# INC-MBPCM1-01.net
KiCad netlist of a schematic drawn in Altium Designer
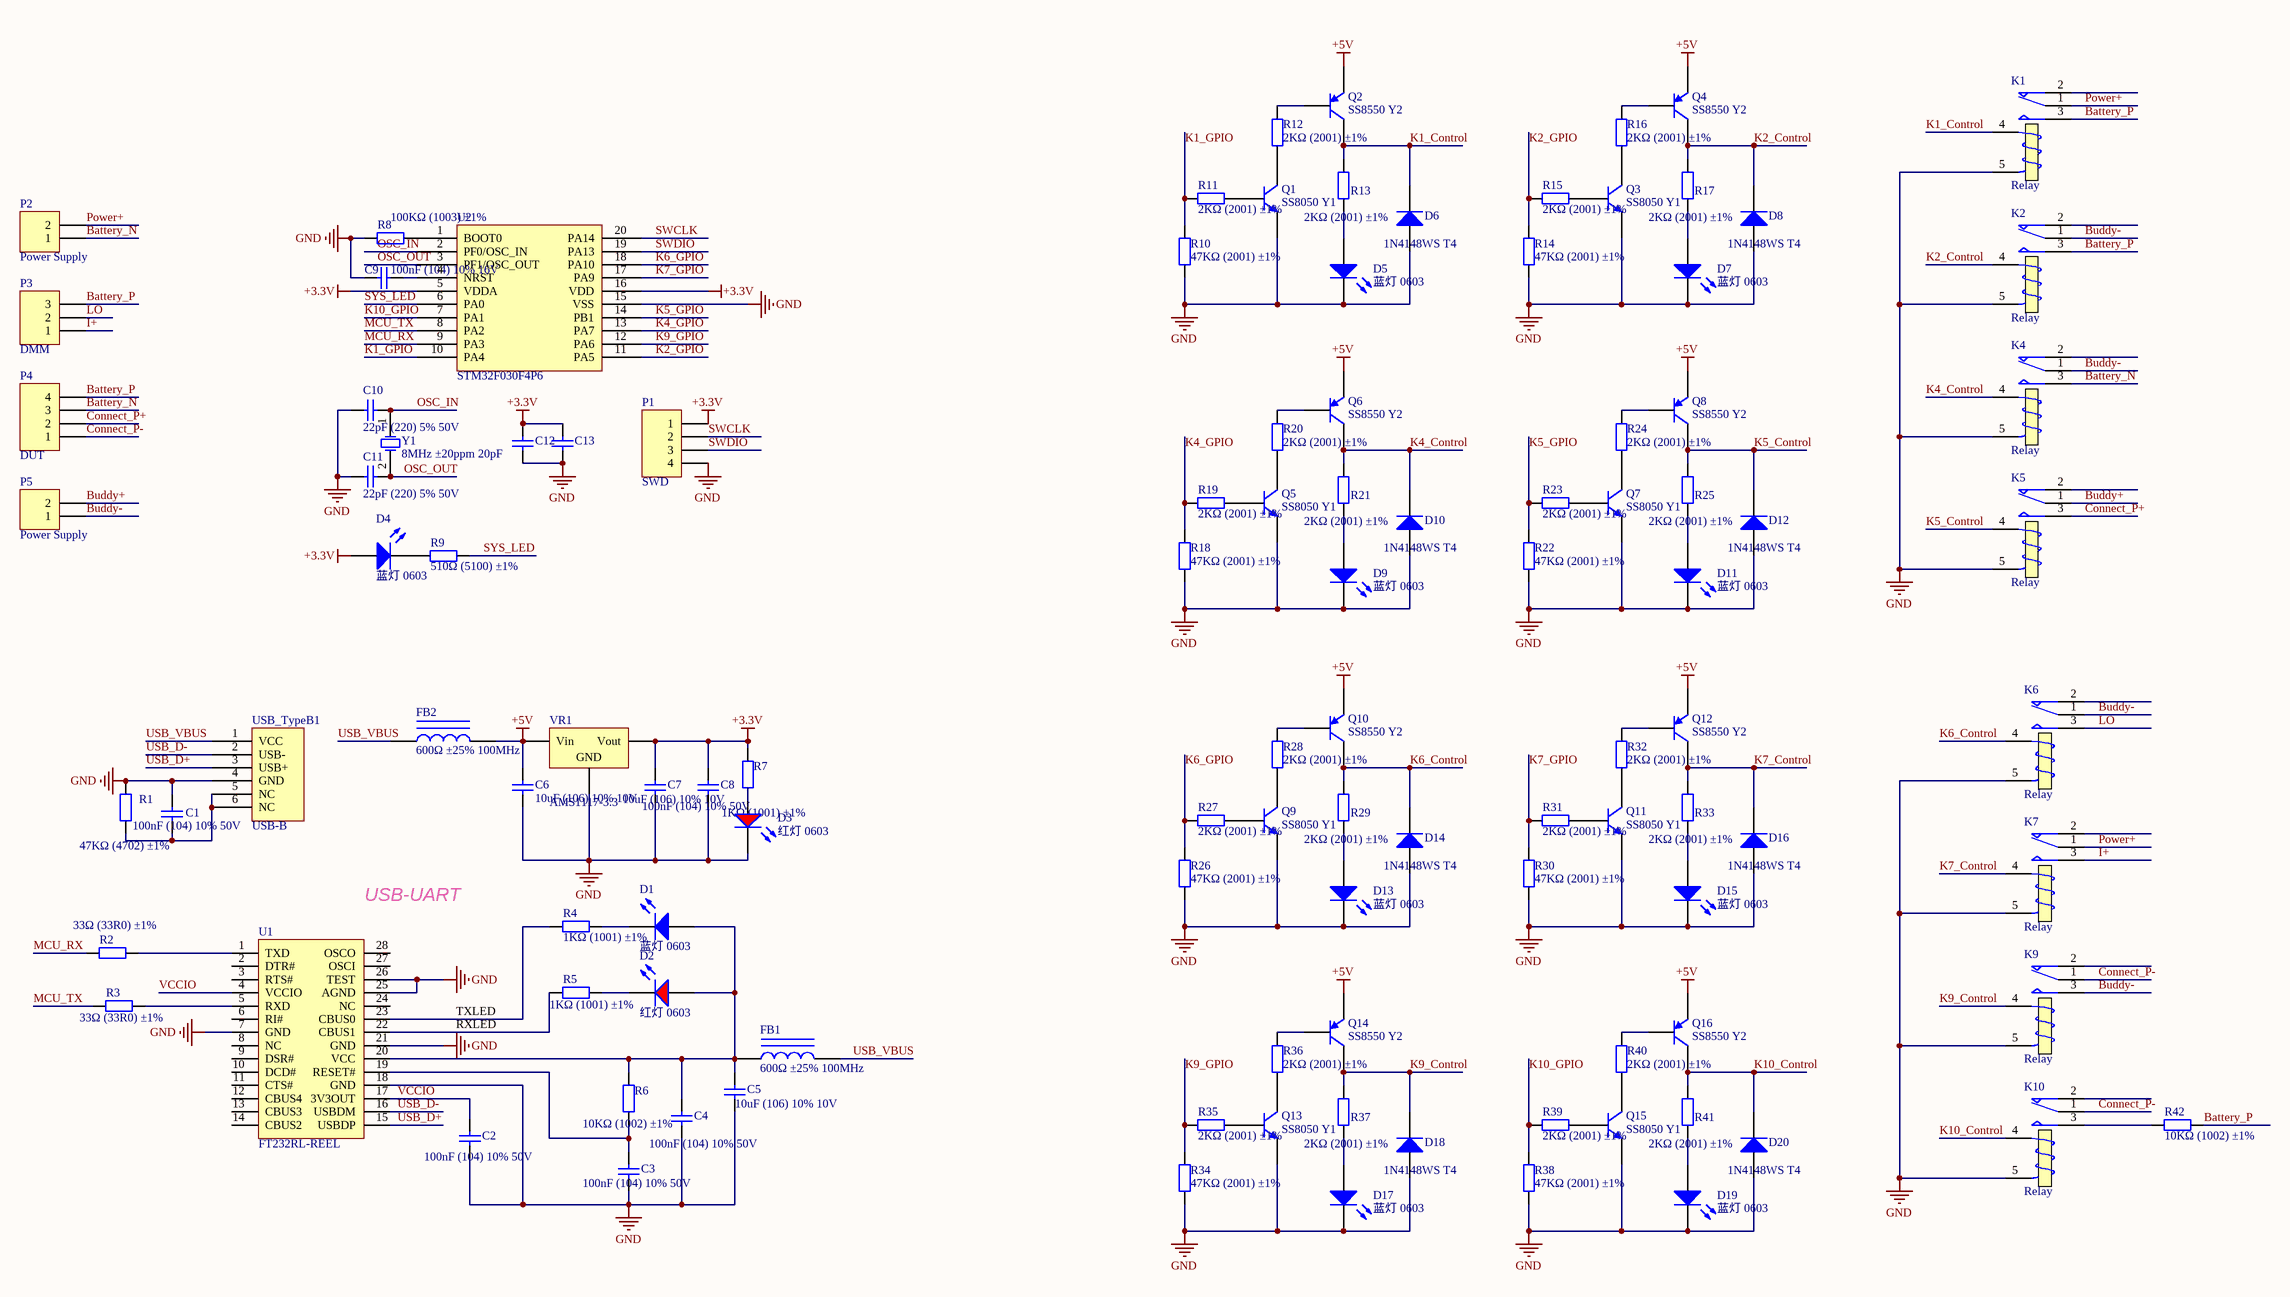
[diagram p0: INC-MBPCM1-01.SchDoc]

(export (version "E")
  (design (tool "Eeschema 10.0.6"))
  (components
    (comp (ref "C1")
      (value "100nF (104) 10% 50V")
      (footprint "0603_C")
      (description "贴片电容")
      (libsource (lib "Miscellaneous Devices LC") (part "0603 100nF (104) 10% 50V"))
    )
    (comp (ref "C2")
      (value "100nF (104) 10% 50V")
      (footprint "0603_C")
      (description "贴片电容")
      (libsource (lib "Miscellaneous Devices LC") (part "0603 100nF (104) 10% 50V"))
    )
    (comp (ref "C3")
      (value "100nF (104) 10% 50V")
      (footprint "0603_C")
      (description "贴片电容")
      (libsource (lib "Miscellaneous Devices LC") (part "0603 100nF (104) 10% 50V"))
    )
    (comp (ref "C4")
      (value "100nF (104) 10% 50V")
      (footprint "0603_C")
      (description "贴片电容")
      (libsource (lib "Miscellaneous Devices LC") (part "0603 100nF (104) 10% 50V"))
    )
    (comp (ref "C5")
      (value "10uF (106) 10% 10V")
      (footprint "0603_C")
      (description "贴片电容")
      (libsource (lib "Miscellaneous Devices LC") (part "0603 10uF (106) 10% 10V"))
    )
    (comp (ref "C6")
      (value "10uF (106) 10% 10V")
      (footprint "0603_C")
      (description "贴片电容")
      (libsource (lib "Miscellaneous Devices LC") (part "0603 10uF (106) 10% 10V"))
    )
    (comp (ref "C7")
      (value "10uF (106) 10% 10V")
      (footprint "0603_C")
      (description "贴片电容")
      (libsource (lib "Miscellaneous Devices LC") (part "0603 10uF (106) 10% 10V"))
    )
    (comp (ref "C8")
      (value "100nF (104) 10% 50V")
      (footprint "0603_C")
      (description "贴片电容")
      (libsource (lib "Miscellaneous Devices LC") (part "0603 100nF (104) 10% 50V"))
    )
    (comp (ref "C9")
      (value "100nF (104) 10% 16V")
      (footprint "0402_C")
      (description "贴片电容")
      (libsource (lib "Miscellaneous Devices LC") (part "0402 100nF (104) 10% 16V"))
    )
    (comp (ref "C10")
      (value "22pF (220) 5% 50V")
      (footprint "0603_C")
      (description "贴片电容")
      (libsource (lib "Miscellaneous Devices LC") (part "0603 22pF (220) 5% 50V"))
    )
    (comp (ref "C11")
      (value "22pF (220) 5% 50V")
      (footprint "0603_C")
      (description "贴片电容")
      (libsource (lib "Miscellaneous Devices LC") (part "0603 22pF (220) 5% 50V"))
    )
    (comp (ref "C12")
      (value "100nF (104) 10% 16V")
      (footprint "0402_C")
      (description "贴片电容")
      (libsource (lib "Miscellaneous Devices LC") (part "0402 100nF (104) 10% 16V"))
    )
    (comp (ref "C13")
      (value "100nF (104) 10% 16V")
      (footprint "0402_C")
      (description "贴片电容")
      (libsource (lib "Miscellaneous Devices LC") (part "0402 100nF (104) 10% 16V"))
    )
    (comp (ref "D1")
      (value "蓝灯 0603")
      (footprint "0603_LED_S1")
      (description "发光二极管")
      (libsource (lib "Miscellaneous Devices LC") (part "0603 蓝灯"))
    )
    (comp (ref "D2")
      (value "红灯 0603")
      (footprint "0603_LED_S1")
      (description "发光二极管")
      (libsource (lib "Miscellaneous Devices LC") (part "0603 红灯"))
    )
    (comp (ref "D3")
      (value "红灯 0603")
      (footprint "0603_LED_S1")
      (description "发光二极管")
      (libsource (lib "Miscellaneous Devices LC") (part "0603 红灯"))
    )
    (comp (ref "D4")
      (value "蓝灯 0603")
      (footprint "0603_LED_S1")
      (description "发光二极管")
      (libsource (lib "Miscellaneous Devices LC") (part "0603 蓝灯"))
    )
    (comp (ref "D5")
      (value "蓝灯 0603")
      (footprint "0603_LED_S1")
      (description "发光二极管")
      (libsource (lib "Miscellaneous Devices LC") (part "0603 蓝灯"))
    )
    (comp (ref "D6")
      (value "1N4148WS T4")
      (footprint "SOD-323")
      (description "二极管")
      (libsource (lib "Miscellaneous Devices LC") (part "SOD-323 1N4148WS T4"))
    )
    (comp (ref "D7")
      (value "蓝灯 0603")
      (footprint "0603_LED_S1")
      (description "发光二极管")
      (libsource (lib "Miscellaneous Devices LC") (part "0603 蓝灯"))
    )
    (comp (ref "D8")
      (value "1N4148WS T4")
      (footprint "SOD-323")
      (description "二极管")
      (libsource (lib "Miscellaneous Devices LC") (part "SOD-323 1N4148WS T4"))
    )
    (comp (ref "D9")
      (value "蓝灯 0603")
      (footprint "0603_LED_S1")
      (description "发光二极管")
      (libsource (lib "Miscellaneous Devices LC") (part "0603 蓝灯"))
    )
    (comp (ref "D10")
      (value "1N4148WS T4")
      (footprint "SOD-323")
      (description "二极管")
      (libsource (lib "Miscellaneous Devices LC") (part "SOD-323 1N4148WS T4"))
    )
    (comp (ref "D11")
      (value "蓝灯 0603")
      (footprint "0603_LED_S1")
      (description "发光二极管")
      (libsource (lib "Miscellaneous Devices LC") (part "0603 蓝灯"))
    )
    (comp (ref "D12")
      (value "1N4148WS T4")
      (footprint "SOD-323")
      (description "二极管")
      (libsource (lib "Miscellaneous Devices LC") (part "SOD-323 1N4148WS T4"))
    )
    (comp (ref "D13")
      (value "蓝灯 0603")
      (footprint "0603_LED_S1")
      (description "发光二极管")
      (libsource (lib "Miscellaneous Devices LC") (part "0603 蓝灯"))
    )
    (comp (ref "D14")
      (value "1N4148WS T4")
      (footprint "SOD-323")
      (description "二极管")
      (libsource (lib "Miscellaneous Devices LC") (part "SOD-323 1N4148WS T4"))
    )
    (comp (ref "D15")
      (value "蓝灯 0603")
      (footprint "0603_LED_S1")
      (description "发光二极管")
      (libsource (lib "Miscellaneous Devices LC") (part "0603 蓝灯"))
    )
    (comp (ref "D16")
      (value "1N4148WS T4")
      (footprint "SOD-323")
      (description "二极管")
      (libsource (lib "Miscellaneous Devices LC") (part "SOD-323 1N4148WS T4"))
    )
    (comp (ref "D17")
      (value "蓝灯 0603")
      (footprint "0603_LED_S1")
      (description "发光二极管")
      (libsource (lib "Miscellaneous Devices LC") (part "0603 蓝灯"))
    )
    (comp (ref "D18")
      (value "1N4148WS T4")
      (footprint "SOD-323")
      (description "二极管")
      (libsource (lib "Miscellaneous Devices LC") (part "SOD-323 1N4148WS T4"))
    )
    (comp (ref "D19")
      (value "蓝灯 0603")
      (footprint "0603_LED_S1")
      (description "发光二极管")
      (libsource (lib "Miscellaneous Devices LC") (part "0603 蓝灯"))
    )
    (comp (ref "D20")
      (value "1N4148WS T4")
      (footprint "SOD-323")
      (description "二极管")
      (libsource (lib "Miscellaneous Devices LC") (part "SOD-323 1N4148WS T4"))
    )
    (comp (ref "FB1")
      (value "600Ω ±25% 100MHz")
      (footprint "0805_L")
      (description "贴片磁珠")
      (libsource (lib "Miscellaneous Devices LC") (part "0805 600Ω 25% 100MHz"))
    )
    (comp (ref "FB2")
      (value "600Ω ±25% 100MHz")
      (footprint "0805_L")
      (description "贴片磁珠")
      (libsource (lib "Miscellaneous Devices LC") (part "0805 600Ω 25% 100MHz"))
    )
    (comp (ref "K1")
      (value "Relay")
      (footprint "插件继电器 G5V-1")
      (description "SPDT Relay")
      (fields (field (name "PUBLISHER") "Altium Limited"))
      (libsource (lib "Miscellaneous Devices") (part "Relay"))
    )
    (comp (ref "K2")
      (value "Relay")
      (footprint "插件继电器 G5V-1")
      (description "SPDT Relay")
      (fields (field (name "PUBLISHER") "Altium Limited"))
      (libsource (lib "Miscellaneous Devices") (part "Relay"))
    )
    (comp (ref "K4")
      (value "Relay")
      (footprint "插件继电器 G5V-1")
      (description "SPDT Relay")
      (fields (field (name "PUBLISHER") "Altium Limited"))
      (libsource (lib "Miscellaneous Devices") (part "Relay"))
    )
    (comp (ref "K5")
      (value "Relay")
      (footprint "插件继电器 G5V-1")
      (description "SPDT Relay")
      (fields (field (name "PUBLISHER") "Altium Limited"))
      (libsource (lib "Miscellaneous Devices") (part "Relay"))
    )
    (comp (ref "K6")
      (value "Relay")
      (footprint "插件继电器 G5V-1")
      (description "SPDT Relay")
      (fields (field (name "PUBLISHER") "Altium Limited"))
      (libsource (lib "Miscellaneous Devices") (part "Relay"))
    )
    (comp (ref "K7")
      (value "Relay")
      (footprint "插件继电器 G5V-1")
      (description "SPDT Relay")
      (fields (field (name "PUBLISHER") "Altium Limited"))
      (libsource (lib "Miscellaneous Devices") (part "Relay"))
    )
    (comp (ref "K9")
      (value "Relay")
      (footprint "插件继电器 G5V-1")
      (description "SPDT Relay")
      (fields (field (name "PUBLISHER") "Altium Limited"))
      (libsource (lib "Miscellaneous Devices") (part "Relay"))
    )
    (comp (ref "K10")
      (value "Relay")
      (footprint "插件继电器 G5V-1")
      (description "SPDT Relay")
      (fields (field (name "PUBLISHER") "Altium Limited"))
      (libsource (lib "Miscellaneous Devices") (part "Relay"))
    )
    (comp (ref "P1")
      (value "SWD")
      (footprint "XH连接器 4P-2.5")
      (description "Header, 4-Pin")
      (fields (field (name "PUBLISHER") "Altium Limited"))
      (libsource (lib "Miscellaneous Connectors") (part "MHDR1X4"))
    )
    (comp (ref "P2")
      (value "Header 2")
      (footprint "WJ15EDGVC-3.81-2P")
      (description "Header, 2-Pin")
      (fields (field (name "PUBLISHER") "Altium Limited"))
      (libsource (lib "Miscellaneous Connectors") (part "Header 2"))
    )
    (comp (ref "P3")
      (value "Header 3")
      (footprint "WJ15EDGVC-3.81-3P")
      (description "Header, 3-Pin")
      (fields (field (name "PUBLISHER") "Altium Limited"))
      (libsource (lib "Miscellaneous Connectors") (part "Header 3"))
    )
    (comp (ref "P4")
      (value "Header 4")
      (footprint "WJ15EDGVC-3.81-4P")
      (description "Header, 4-Pin")
      (fields (field (name "PUBLISHER") "Altium Limited"))
      (libsource (lib "Miscellaneous Connectors") (part "Header 4"))
    )
    (comp (ref "P5")
      (value "Header 2")
      (footprint "WJ15EDGVC-3.81-2P")
      (description "Header, 2-Pin")
      (fields (field (name "PUBLISHER") "Altium Limited"))
      (libsource (lib "Miscellaneous Connectors") (part "Header 2"))
    )
    (comp (ref "Q1")
      (value "SS8050 Y1")
      (footprint "SOT-23(SOT-23-3)")
      (description "三极管")
      (libsource (lib "Miscellaneous Devices LC") (part "SOT-23 SS8050 Y1"))
    )
    (comp (ref "Q2")
      (value "SS8550 Y2")
      (footprint "SOT-23(SOT-23-3)")
      (description "三极管")
      (libsource (lib "Miscellaneous Devices LC") (part "SOT-23 SS8550 Y2"))
    )
    (comp (ref "Q3")
      (value "SS8050 Y1")
      (footprint "SOT-23(SOT-23-3)")
      (description "三极管")
      (libsource (lib "Miscellaneous Devices LC") (part "SOT-23 SS8050 Y1"))
    )
    (comp (ref "Q4")
      (value "SS8550 Y2")
      (footprint "SOT-23(SOT-23-3)")
      (description "三极管")
      (libsource (lib "Miscellaneous Devices LC") (part "SOT-23 SS8550 Y2"))
    )
    (comp (ref "Q5")
      (value "SS8050 Y1")
      (footprint "SOT-23(SOT-23-3)")
      (description "三极管")
      (libsource (lib "Miscellaneous Devices LC") (part "SOT-23 SS8050 Y1"))
    )
    (comp (ref "Q6")
      (value "SS8550 Y2")
      (footprint "SOT-23(SOT-23-3)")
      (description "三极管")
      (libsource (lib "Miscellaneous Devices LC") (part "SOT-23 SS8550 Y2"))
    )
    (comp (ref "Q7")
      (value "SS8050 Y1")
      (footprint "SOT-23(SOT-23-3)")
      (description "三极管")
      (libsource (lib "Miscellaneous Devices LC") (part "SOT-23 SS8050 Y1"))
    )
    (comp (ref "Q8")
      (value "SS8550 Y2")
      (footprint "SOT-23(SOT-23-3)")
      (description "三极管")
      (libsource (lib "Miscellaneous Devices LC") (part "SOT-23 SS8550 Y2"))
    )
    (comp (ref "Q9")
      (value "SS8050 Y1")
      (footprint "SOT-23(SOT-23-3)")
      (description "三极管")
      (libsource (lib "Miscellaneous Devices LC") (part "SOT-23 SS8050 Y1"))
    )
    (comp (ref "Q10")
      (value "SS8550 Y2")
      (footprint "SOT-23(SOT-23-3)")
      (description "三极管")
      (libsource (lib "Miscellaneous Devices LC") (part "SOT-23 SS8550 Y2"))
    )
    (comp (ref "Q11")
      (value "SS8050 Y1")
      (footprint "SOT-23(SOT-23-3)")
      (description "三极管")
      (libsource (lib "Miscellaneous Devices LC") (part "SOT-23 SS8050 Y1"))
    )
    (comp (ref "Q12")
      (value "SS8550 Y2")
      (footprint "SOT-23(SOT-23-3)")
      (description "三极管")
      (libsource (lib "Miscellaneous Devices LC") (part "SOT-23 SS8550 Y2"))
    )
    (comp (ref "Q13")
      (value "SS8050 Y1")
      (footprint "SOT-23(SOT-23-3)")
      (description "三极管")
      (libsource (lib "Miscellaneous Devices LC") (part "SOT-23 SS8050 Y1"))
    )
    (comp (ref "Q14")
      (value "SS8550 Y2")
      (footprint "SOT-23(SOT-23-3)")
      (description "三极管")
      (libsource (lib "Miscellaneous Devices LC") (part "SOT-23 SS8550 Y2"))
    )
    (comp (ref "Q15")
      (value "SS8050 Y1")
      (footprint "SOT-23(SOT-23-3)")
      (description "三极管")
      (libsource (lib "Miscellaneous Devices LC") (part "SOT-23 SS8050 Y1"))
    )
    (comp (ref "Q16")
      (value "SS8550 Y2")
      (footprint "SOT-23(SOT-23-3)")
      (description "三极管")
      (libsource (lib "Miscellaneous Devices LC") (part "SOT-23 SS8550 Y2"))
    )
    (comp (ref "R1")
      (value "47KΩ (4702) ±1%")
      (footprint "0603_R")
      (description "贴片电阻")
      (libsource (lib "Miscellaneous Devices LC") (part "0603 47KΩ (4702) 1%"))
    )
    (comp (ref "R2")
      (value "33Ω (33R0) ±1%")
      (footprint "0603_R")
      (description "贴片电阻")
      (libsource (lib "Miscellaneous Devices LC") (part "0603 330Ω (3300) 1%"))
    )
    (comp (ref "R3")
      (value "33Ω (33R0) ±1%")
      (footprint "0603_R")
      (description "贴片电阻")
      (libsource (lib "Miscellaneous Devices LC") (part "0603 330Ω (3300) 1%"))
    )
    (comp (ref "R4")
      (value "1KΩ (1001) ±1%")
      (footprint "0603_R")
      (description "贴片电阻")
      (libsource (lib "") (part "0603 1KΩ (1001) 1%_2"))
    )
    (comp (ref "R5")
      (value "1KΩ (1001) ±1%")
      (footprint "0603_R")
      (description "贴片电阻")
      (libsource (lib "Miscellaneous Devices LC") (part "0603 1KΩ (1001) 1%"))
    )
    (comp (ref "R6")
      (value "10KΩ (1002) ±1%")
      (footprint "0603_R")
      (description "贴片电阻")
      (libsource (lib "Miscellaneous Devices LC") (part "0603 10KΩ (1002) 1%"))
    )
    (comp (ref "R7")
      (value "1KΩ (1001) ±1%")
      (footprint "0603_R")
      (description "贴片电阻")
      (libsource (lib "") (part "0603 1KΩ (1001) 1%_1"))
    )
    (comp (ref "R8")
      (value "100KΩ (1003) ±1%")
      (footprint "0402_R")
      (description "贴片电阻")
      (libsource (lib "Miscellaneous Devices LC") (part "0402 100KΩ (1003) 1%"))
    )
    (comp (ref "R9")
      (value "510Ω (5100) ±1%")
      (footprint "0603_R")
      (description "贴片电阻")
      (libsource (lib "Miscellaneous Devices LC") (part "0603 510Ω (5100) 1%"))
    )
    (comp (ref "R10")
      (value "47KΩ (2001) ±1%")
      (footprint "0603_R")
      (description "贴片电阻")
      (libsource (lib "") (part "0603 2KΩ (2001) 1%_1"))
    )
    (comp (ref "R11")
      (value "2KΩ (2001) ±1%")
      (footprint "0603_R")
      (description "贴片电阻")
      (libsource (lib "Miscellaneous Devices LC") (part "0603 2KΩ (2001) 1%"))
    )
    (comp (ref "R12")
      (value "2KΩ (2001) ±1%")
      (footprint "0603_R")
      (description "贴片电阻")
      (libsource (lib "") (part "0603 2KΩ (2001) 1%_1"))
    )
    (comp (ref "R13")
      (value "2KΩ (2001) ±1%")
      (footprint "0603_R")
      (description "贴片电阻")
      (libsource (lib "") (part "0603 2KΩ (2001) 1%_2"))
    )
    (comp (ref "R14")
      (value "47KΩ (2001) ±1%")
      (footprint "0603_R")
      (description "贴片电阻")
      (libsource (lib "") (part "0603 2KΩ (2001) 1%_1"))
    )
    (comp (ref "R15")
      (value "2KΩ (2001) ±1%")
      (footprint "0603_R")
      (description "贴片电阻")
      (libsource (lib "Miscellaneous Devices LC") (part "0603 2KΩ (2001) 1%"))
    )
    (comp (ref "R16")
      (value "2KΩ (2001) ±1%")
      (footprint "0603_R")
      (description "贴片电阻")
      (libsource (lib "") (part "0603 2KΩ (2001) 1%_1"))
    )
    (comp (ref "R17")
      (value "2KΩ (2001) ±1%")
      (footprint "0603_R")
      (description "贴片电阻")
      (libsource (lib "") (part "0603 2KΩ (2001) 1%_2"))
    )
    (comp (ref "R18")
      (value "47KΩ (2001) ±1%")
      (footprint "0603_R")
      (description "贴片电阻")
      (libsource (lib "") (part "0603 2KΩ (2001) 1%_1"))
    )
    (comp (ref "R19")
      (value "2KΩ (2001) ±1%")
      (footprint "0603_R")
      (description "贴片电阻")
      (libsource (lib "Miscellaneous Devices LC") (part "0603 2KΩ (2001) 1%"))
    )
    (comp (ref "R20")
      (value "2KΩ (2001) ±1%")
      (footprint "0603_R")
      (description "贴片电阻")
      (libsource (lib "") (part "0603 2KΩ (2001) 1%_1"))
    )
    (comp (ref "R21")
      (value "2KΩ (2001) ±1%")
      (footprint "0603_R")
      (description "贴片电阻")
      (libsource (lib "") (part "0603 2KΩ (2001) 1%_2"))
    )
    (comp (ref "R22")
      (value "47KΩ (2001) ±1%")
      (footprint "0603_R")
      (description "贴片电阻")
      (libsource (lib "") (part "0603 2KΩ (2001) 1%_1"))
    )
    (comp (ref "R23")
      (value "2KΩ (2001) ±1%")
      (footprint "0603_R")
      (description "贴片电阻")
      (libsource (lib "Miscellaneous Devices LC") (part "0603 2KΩ (2001) 1%"))
    )
    (comp (ref "R24")
      (value "2KΩ (2001) ±1%")
      (footprint "0603_R")
      (description "贴片电阻")
      (libsource (lib "") (part "0603 2KΩ (2001) 1%_1"))
    )
    (comp (ref "R25")
      (value "2KΩ (2001) ±1%")
      (footprint "0603_R")
      (description "贴片电阻")
      (libsource (lib "") (part "0603 2KΩ (2001) 1%_2"))
    )
    (comp (ref "R26")
      (value "47KΩ (2001) ±1%")
      (footprint "0603_R")
      (description "贴片电阻")
      (libsource (lib "") (part "0603 2KΩ (2001) 1%_1"))
    )
    (comp (ref "R27")
      (value "2KΩ (2001) ±1%")
      (footprint "0603_R")
      (description "贴片电阻")
      (libsource (lib "Miscellaneous Devices LC") (part "0603 2KΩ (2001) 1%"))
    )
    (comp (ref "R28")
      (value "2KΩ (2001) ±1%")
      (footprint "0603_R")
      (description "贴片电阻")
      (libsource (lib "") (part "0603 2KΩ (2001) 1%_1"))
    )
    (comp (ref "R29")
      (value "2KΩ (2001) ±1%")
      (footprint "0603_R")
      (description "贴片电阻")
      (libsource (lib "") (part "0603 2KΩ (2001) 1%_2"))
    )
    (comp (ref "R30")
      (value "47KΩ (2001) ±1%")
      (footprint "0603_R")
      (description "贴片电阻")
      (libsource (lib "") (part "0603 2KΩ (2001) 1%_1"))
    )
    (comp (ref "R31")
      (value "2KΩ (2001) ±1%")
      (footprint "0603_R")
      (description "贴片电阻")
      (libsource (lib "Miscellaneous Devices LC") (part "0603 2KΩ (2001) 1%"))
    )
    (comp (ref "R32")
      (value "2KΩ (2001) ±1%")
      (footprint "0603_R")
      (description "贴片电阻")
      (libsource (lib "") (part "0603 2KΩ (2001) 1%_1"))
    )
    (comp (ref "R33")
      (value "2KΩ (2001) ±1%")
      (footprint "0603_R")
      (description "贴片电阻")
      (libsource (lib "") (part "0603 2KΩ (2001) 1%_2"))
    )
    (comp (ref "R34")
      (value "47KΩ (2001) ±1%")
      (footprint "0603_R")
      (description "贴片电阻")
      (libsource (lib "") (part "0603 2KΩ (2001) 1%_1"))
    )
    (comp (ref "R35")
      (value "2KΩ (2001) ±1%")
      (footprint "0603_R")
      (description "贴片电阻")
      (libsource (lib "Miscellaneous Devices LC") (part "0603 2KΩ (2001) 1%"))
    )
    (comp (ref "R36")
      (value "2KΩ (2001) ±1%")
      (footprint "0603_R")
      (description "贴片电阻")
      (libsource (lib "") (part "0603 2KΩ (2001) 1%_1"))
    )
    (comp (ref "R37")
      (value "2KΩ (2001) ±1%")
      (footprint "0603_R")
      (description "贴片电阻")
      (libsource (lib "") (part "0603 2KΩ (2001) 1%_2"))
    )
    (comp (ref "R38")
      (value "47KΩ (2001) ±1%")
      (footprint "0603_R")
      (description "贴片电阻")
      (libsource (lib "") (part "0603 2KΩ (2001) 1%_1"))
    )
    (comp (ref "R39")
      (value "2KΩ (2001) ±1%")
      (footprint "0603_R")
      (description "贴片电阻")
      (libsource (lib "Miscellaneous Devices LC") (part "0603 2KΩ (2001) 1%"))
    )
    (comp (ref "R40")
      (value "2KΩ (2001) ±1%")
      (footprint "0603_R")
      (description "贴片电阻")
      (libsource (lib "") (part "0603 2KΩ (2001) 1%_1"))
    )
    (comp (ref "R41")
      (value "2KΩ (2001) ±1%")
      (footprint "0603_R")
      (description "贴片电阻")
      (libsource (lib "") (part "0603 2KΩ (2001) 1%_2"))
    )
    (comp (ref "R42")
      (value "10KΩ (1002) ±1%")
      (footprint "0805_R")
      (description "贴片电阻")
      (libsource (lib "Miscellaneous Devices LC") (part "0805 10KΩ (1002) 1%"))
    )
    (comp (ref "U1")
      (value "FT232RL-REEL")
      (footprint "SSOP-28_208mil")
      (libsource (lib "GB-SCH") (part "FT232RL"))
    )
    (comp (ref "U2")
      (value "STM32F030F4P6")
      (footprint "TSSOP-20")
      (description "ARM")
      (libsource (lib "Miscellaneous Devices LC") (part "STM32F030F4P6"))
    )
    (comp (ref "USB_TypeB1")
      (value "USB-B")
      (footprint "USB_TypeB")
      (libsource (lib "GB-SCH") (part "USB-6"))
    )
    (comp (ref "VR1")
      (value "AMS1117-3.3")
      (footprint "SOT-223")
      (description "低压差线性稳压(LDO)")
      (libsource (lib "Miscellaneous Devices LC") (part "SOT-223 AMS1117-3.3"))
    )
    (comp (ref "Y1")
      (value "8MHz ±20ppm 20pF")
      (footprint "SMD-5032_2P")
      (description "贴片晶振")
      (libsource (lib "Miscellaneous Devices LC") (part "SMD-5032_2P 8MHz 20ppm 20pF"))
    )
  )
  (nets
    (net (code "1") (name "+3.3V") (class "Default")
      (node (ref "C12") (pin "2") (pinfunction "2_2") (pintype "passive"))
      (node (ref "C13") (pin "2") (pinfunction "2_2") (pintype "passive"))
      (node (ref "C7") (pin "1") (pinfunction "1_1") (pintype "passive"))
      (node (ref "C8") (pin "2") (pinfunction "2_2") (pintype "passive"))
      (node (ref "D4") (pin "A") (pinfunction "A_A") (pintype "passive"))
      (node (ref "P1") (pin "1") (pinfunction "1_1") (pintype "passive"))
      (node (ref "R7") (pin "1") (pinfunction "1_1") (pintype "passive"))
      (node (ref "U2") (pin "16") (pinfunction "VDD_16") (pintype "passive"))
      (node (ref "U2") (pin "5") (pinfunction "VDDA_5") (pintype "passive"))
      (node (ref "VR1") (pin "2") (pinfunction "Vout_2") (pintype "passive"))
    )
    (net (code "2") (name "+5V") (class "Default")
      (node (ref "C6") (pin "2") (pinfunction "2_2") (pintype "passive"))
      (node (ref "FB2") (pin "2") (pinfunction "2_2") (pintype "passive"))
      (node (ref "Q10") (pin "2") (pinfunction "E_2") (pintype "passive"))
      (node (ref "Q12") (pin "2") (pinfunction "E_2") (pintype "passive"))
      (node (ref "Q14") (pin "2") (pinfunction "E_2") (pintype "passive"))
      (node (ref "Q16") (pin "2") (pinfunction "E_2") (pintype "passive"))
      (node (ref "Q2") (pin "2") (pinfunction "E_2") (pintype "passive"))
      (node (ref "Q4") (pin "2") (pinfunction "E_2") (pintype "passive"))
      (node (ref "Q6") (pin "2") (pinfunction "E_2") (pintype "passive"))
      (node (ref "Q8") (pin "2") (pinfunction "E_2") (pintype "passive"))
      (node (ref "VR1") (pin "3") (pinfunction "Vin_3") (pintype "passive"))
    )
    (net (code "3") (name "/Battery_N") (class "Default")
      (node (ref "K4") (pin "3") (pinfunction "NO_3") (pintype "passive"))
      (node (ref "P2") (pin "1") (pinfunction "1_1") (pintype "passive"))
      (node (ref "P4") (pin "3") (pinfunction "3_3") (pintype "passive"))
    )
    (net (code "4") (name "/Battery_P") (class "Default")
      (node (ref "K1") (pin "3") (pinfunction "NO_3") (pintype "passive"))
      (node (ref "K2") (pin "3") (pinfunction "NO_3") (pintype "passive"))
      (node (ref "P3") (pin "3") (pinfunction "3_3") (pintype "passive"))
      (node (ref "P4") (pin "4") (pinfunction "4_4") (pintype "passive"))
      (node (ref "R42") (pin "2") (pinfunction "2_2") (pintype "passive"))
    )
    (net (code "5") (name "/Buddy+") (class "Default")
      (node (ref "K5") (pin "1") (pinfunction "COM_1") (pintype "passive"))
      (node (ref "P5") (pin "2") (pinfunction "2_2") (pintype "passive"))
    )
    (net (code "6") (name "/Buddy-") (class "Default")
      (node (ref "K2") (pin "1") (pinfunction "COM_1") (pintype "passive"))
      (node (ref "K4") (pin "1") (pinfunction "COM_1") (pintype "passive"))
      (node (ref "K6") (pin "1") (pinfunction "COM_1") (pintype "passive"))
      (node (ref "K9") (pin "3") (pinfunction "NO_3") (pintype "passive"))
      (node (ref "P5") (pin "1") (pinfunction "1_1") (pintype "passive"))
    )
    (net (code "7") (name "/Connect_P+") (class "Default")
      (node (ref "K5") (pin "3") (pinfunction "NO_3") (pintype "passive"))
      (node (ref "P4") (pin "2") (pinfunction "2_2") (pintype "passive"))
    )
    (net (code "8") (name "/Connect_P-") (class "Default")
      (node (ref "K10") (pin "1") (pinfunction "COM_1") (pintype "passive"))
      (node (ref "K9") (pin "1") (pinfunction "COM_1") (pintype "passive"))
      (node (ref "P4") (pin "1") (pinfunction "1_1") (pintype "passive"))
    )
    (net (code "9") (name "/I+") (class "Default")
      (node (ref "K7") (pin "3") (pinfunction "NO_3") (pintype "passive"))
      (node (ref "P3") (pin "1") (pinfunction "1_1") (pintype "passive"))
    )
    (net (code "10") (name "/K1_Control") (class "Default")
      (node (ref "D6") (pin "2") (pinfunction "K_2") (pintype "passive"))
      (node (ref "K1") (pin "4") (pinfunction "T1_4") (pintype "passive"))
      (node (ref "Q2") (pin "3") (pinfunction "C_3") (pintype "passive"))
      (node (ref "R13") (pin "1") (pinfunction "1_1") (pintype "passive"))
    )
    (net (code "11") (name "/K1_GPIO") (class "Default")
      (node (ref "R10") (pin "2") (pinfunction "2_2") (pintype "passive"))
      (node (ref "R11") (pin "2") (pinfunction "2_2") (pintype "passive"))
      (node (ref "U2") (pin "10") (pinfunction "PA4_10") (pintype "passive"))
    )
    (net (code "12") (name "/K2_Control") (class "Default")
      (node (ref "D8") (pin "2") (pinfunction "K_2") (pintype "passive"))
      (node (ref "K2") (pin "4") (pinfunction "T1_4") (pintype "passive"))
      (node (ref "Q4") (pin "3") (pinfunction "C_3") (pintype "passive"))
      (node (ref "R17") (pin "1") (pinfunction "1_1") (pintype "passive"))
    )
    (net (code "13") (name "/K2_GPIO") (class "Default")
      (node (ref "R14") (pin "2") (pinfunction "2_2") (pintype "passive"))
      (node (ref "R15") (pin "2") (pinfunction "2_2") (pintype "passive"))
      (node (ref "U2") (pin "11") (pinfunction "PA5_11") (pintype "passive"))
    )
    (net (code "14") (name "/K4_Control") (class "Default")
      (node (ref "D10") (pin "2") (pinfunction "K_2") (pintype "passive"))
      (node (ref "K4") (pin "4") (pinfunction "T1_4") (pintype "passive"))
      (node (ref "Q6") (pin "3") (pinfunction "C_3") (pintype "passive"))
      (node (ref "R21") (pin "1") (pinfunction "1_1") (pintype "passive"))
    )
    (net (code "15") (name "/K4_GPIO") (class "Default")
      (node (ref "R18") (pin "2") (pinfunction "2_2") (pintype "passive"))
      (node (ref "R19") (pin "2") (pinfunction "2_2") (pintype "passive"))
      (node (ref "U2") (pin "13") (pinfunction "PA7_13") (pintype "passive"))
    )
    (net (code "16") (name "/K5_Control") (class "Default")
      (node (ref "D12") (pin "2") (pinfunction "K_2") (pintype "passive"))
      (node (ref "K5") (pin "4") (pinfunction "T1_4") (pintype "passive"))
      (node (ref "Q8") (pin "3") (pinfunction "C_3") (pintype "passive"))
      (node (ref "R25") (pin "1") (pinfunction "1_1") (pintype "passive"))
    )
    (net (code "17") (name "/K5_GPIO") (class "Default")
      (node (ref "R22") (pin "2") (pinfunction "2_2") (pintype "passive"))
      (node (ref "R23") (pin "2") (pinfunction "2_2") (pintype "passive"))
      (node (ref "U2") (pin "14") (pinfunction "PB1_14") (pintype "passive"))
    )
    (net (code "18") (name "/K6_Control") (class "Default")
      (node (ref "D14") (pin "2") (pinfunction "K_2") (pintype "passive"))
      (node (ref "K6") (pin "4") (pinfunction "T1_4") (pintype "passive"))
      (node (ref "Q10") (pin "3") (pinfunction "C_3") (pintype "passive"))
      (node (ref "R29") (pin "1") (pinfunction "1_1") (pintype "passive"))
    )
    (net (code "19") (name "/K6_GPIO") (class "Default")
      (node (ref "R26") (pin "2") (pinfunction "2_2") (pintype "passive"))
      (node (ref "R27") (pin "2") (pinfunction "2_2") (pintype "passive"))
      (node (ref "U2") (pin "18") (pinfunction "PA10_18") (pintype "passive"))
    )
    (net (code "20") (name "/K7_Control") (class "Default")
      (node (ref "D16") (pin "2") (pinfunction "K_2") (pintype "passive"))
      (node (ref "K7") (pin "4") (pinfunction "T1_4") (pintype "passive"))
      (node (ref "Q12") (pin "3") (pinfunction "C_3") (pintype "passive"))
      (node (ref "R33") (pin "1") (pinfunction "1_1") (pintype "passive"))
    )
    (net (code "21") (name "/K7_GPIO") (class "Default")
      (node (ref "R30") (pin "2") (pinfunction "2_2") (pintype "passive"))
      (node (ref "R31") (pin "2") (pinfunction "2_2") (pintype "passive"))
      (node (ref "U2") (pin "17") (pinfunction "PA9_17") (pintype "passive"))
    )
    (net (code "22") (name "/K9_Control") (class "Default")
      (node (ref "D18") (pin "2") (pinfunction "K_2") (pintype "passive"))
      (node (ref "K9") (pin "4") (pinfunction "T1_4") (pintype "passive"))
      (node (ref "Q14") (pin "3") (pinfunction "C_3") (pintype "passive"))
      (node (ref "R37") (pin "1") (pinfunction "1_1") (pintype "passive"))
    )
    (net (code "23") (name "/K9_GPIO") (class "Default")
      (node (ref "R34") (pin "2") (pinfunction "2_2") (pintype "passive"))
      (node (ref "R35") (pin "2") (pinfunction "2_2") (pintype "passive"))
      (node (ref "U2") (pin "12") (pinfunction "PA6_12") (pintype "passive"))
    )
    (net (code "24") (name "/K10_Control") (class "Default")
      (node (ref "D20") (pin "2") (pinfunction "K_2") (pintype "passive"))
      (node (ref "K10") (pin "4") (pinfunction "T1_4") (pintype "passive"))
      (node (ref "Q16") (pin "3") (pinfunction "C_3") (pintype "passive"))
      (node (ref "R41") (pin "1") (pinfunction "1_1") (pintype "passive"))
    )
    (net (code "25") (name "/K10_GPIO") (class "Default")
      (node (ref "R38") (pin "2") (pinfunction "2_2") (pintype "passive"))
      (node (ref "R39") (pin "2") (pinfunction "2_2") (pintype "passive"))
      (node (ref "U2") (pin "7") (pinfunction "PA1_7") (pintype "passive"))
    )
    (net (code "26") (name "/LO") (class "Default")
      (node (ref "K6") (pin "3") (pinfunction "NO_3") (pintype "passive"))
      (node (ref "P3") (pin "2") (pinfunction "2_2") (pintype "passive"))
    )
    (net (code "27") (name "/MCU_RX") (class "Default")
      (node (ref "R2") (pin "1") (pinfunction "1_1") (pintype "passive"))
      (node (ref "U2") (pin "9") (pinfunction "PA3_9") (pintype "passive"))
    )
    (net (code "28") (name "/MCU_TX") (class "Default")
      (node (ref "R3") (pin "1") (pinfunction "1_1") (pintype "passive"))
      (node (ref "U2") (pin "8") (pinfunction "PA2_8") (pintype "passive"))
    )
    (net (code "29") (name "/OSC_IN") (class "Default")
      (node (ref "C10") (pin "2") (pinfunction "2_2") (pintype "passive"))
      (node (ref "U2") (pin "2") (pinfunction "PF0/OSC_IN_2") (pintype "passive"))
      (node (ref "Y1") (pin "1") (pinfunction "OSC1_1") (pintype "passive"))
    )
    (net (code "30") (name "/OSC_OUT") (class "Default")
      (node (ref "C11") (pin "2") (pinfunction "2_2") (pintype "passive"))
      (node (ref "U2") (pin "3") (pinfunction "PF1/OSC_OUT_3") (pintype "passive"))
      (node (ref "Y1") (pin "2") (pinfunction "OSC2_2") (pintype "passive"))
    )
    (net (code "31") (name "/Power+") (class "Default")
      (node (ref "K1") (pin "1") (pinfunction "COM_1") (pintype "passive"))
      (node (ref "K7") (pin "1") (pinfunction "COM_1") (pintype "passive"))
      (node (ref "P2") (pin "2") (pinfunction "2_2") (pintype "passive"))
    )
    (net (code "32") (name "/SWCLK") (class "Default")
      (node (ref "P1") (pin "2") (pinfunction "2_2") (pintype "passive"))
      (node (ref "U2") (pin "20") (pinfunction "PA14_20") (pintype "passive"))
    )
    (net (code "33") (name "/SWDIO") (class "Default")
      (node (ref "P1") (pin "3") (pinfunction "3_3") (pintype "passive"))
      (node (ref "U2") (pin "19") (pinfunction "PA13_19") (pintype "passive"))
    )
    (net (code "34") (name "/SYS_LED") (class "Default")
      (node (ref "R9") (pin "2") (pinfunction "2_2") (pintype "passive"))
      (node (ref "U2") (pin "6") (pinfunction "PA0_6") (pintype "passive"))
    )
    (net (code "35") (name "/USB_D+") (class "Default")
      (node (ref "U1") (pin "15") (pinfunction "USBDP_15") (pintype "passive"))
      (node (ref "USB_TypeB1") (pin "3") (pinfunction "USB+_3") (pintype "passive"))
    )
    (net (code "36") (name "/USB_D-") (class "Default")
      (node (ref "U1") (pin "16") (pinfunction "USBDM_16") (pintype "passive"))
      (node (ref "USB_TypeB1") (pin "2") (pinfunction "USB-_2") (pintype "passive"))
    )
    (net (code "37") (name "/USB_VBUS") (class "Default")
      (node (ref "FB1") (pin "2") (pinfunction "2_2") (pintype "passive"))
      (node (ref "FB2") (pin "1") (pinfunction "1_1") (pintype "passive"))
      (node (ref "USB_TypeB1") (pin "1") (pinfunction "VCC_1") (pintype "passive"))
    )
    (net (code "38") (name "/VCCIO") (class "Default")
      (node (ref "C2") (pin "1") (pinfunction "1_1") (pintype "passive"))
      (node (ref "U1") (pin "17") (pinfunction "3V3OUT_17") (pintype "passive"))
      (node (ref "U1") (pin "4") (pinfunction "VCCIO_4") (pintype "passive"))
    )
    (net (code "39") (name "GND") (class "Default")
      (node (ref "C1") (pin "2") (pinfunction "2_2") (pintype "passive"))
      (node (ref "C10") (pin "1") (pinfunction "1_1") (pintype "passive"))
      (node (ref "C11") (pin "1") (pinfunction "1_1") (pintype "passive"))
      (node (ref "C12") (pin "1") (pinfunction "1_1") (pintype "passive"))
      (node (ref "C13") (pin "1") (pinfunction "1_1") (pintype "passive"))
      (node (ref "C2") (pin "2") (pinfunction "2_2") (pintype "passive"))
      (node (ref "C3") (pin "2") (pinfunction "2_2") (pintype "passive"))
      (node (ref "C4") (pin "1") (pinfunction "1_1") (pintype "passive"))
      (node (ref "C5") (pin "1") (pinfunction "1_1") (pintype "passive"))
      (node (ref "C6") (pin "1") (pinfunction "1_1") (pintype "passive"))
      (node (ref "C7") (pin "2") (pinfunction "2_2") (pintype "passive"))
      (node (ref "C8") (pin "1") (pinfunction "1_1") (pintype "passive"))
      (node (ref "C9") (pin "2") (pinfunction "2_2") (pintype "passive"))
      (node (ref "D10") (pin "1") (pinfunction "A_1") (pintype "passive"))
      (node (ref "D11") (pin "K") (pinfunction "K_K") (pintype "passive"))
      (node (ref "D12") (pin "1") (pinfunction "A_1") (pintype "passive"))
      (node (ref "D13") (pin "K") (pinfunction "K_K") (pintype "passive"))
      (node (ref "D14") (pin "1") (pinfunction "A_1") (pintype "passive"))
      (node (ref "D15") (pin "K") (pinfunction "K_K") (pintype "passive"))
      (node (ref "D16") (pin "1") (pinfunction "A_1") (pintype "passive"))
      (node (ref "D17") (pin "K") (pinfunction "K_K") (pintype "passive"))
      (node (ref "D18") (pin "1") (pinfunction "A_1") (pintype "passive"))
      (node (ref "D19") (pin "K") (pinfunction "K_K") (pintype "passive"))
      (node (ref "D20") (pin "1") (pinfunction "A_1") (pintype "passive"))
      (node (ref "D3") (pin "K") (pinfunction "K_K") (pintype "passive"))
      (node (ref "D5") (pin "K") (pinfunction "K_K") (pintype "passive"))
      (node (ref "D6") (pin "1") (pinfunction "A_1") (pintype "passive"))
      (node (ref "D7") (pin "K") (pinfunction "K_K") (pintype "passive"))
      (node (ref "D8") (pin "1") (pinfunction "A_1") (pintype "passive"))
      (node (ref "D9") (pin "K") (pinfunction "K_K") (pintype "passive"))
      (node (ref "K1") (pin "5") (pinfunction "T2_5") (pintype "passive"))
      (node (ref "K10") (pin "5") (pinfunction "T2_5") (pintype "passive"))
      (node (ref "K2") (pin "5") (pinfunction "T2_5") (pintype "passive"))
      (node (ref "K4") (pin "5") (pinfunction "T2_5") (pintype "passive"))
      (node (ref "K5") (pin "5") (pinfunction "T2_5") (pintype "passive"))
      (node (ref "K6") (pin "5") (pinfunction "T2_5") (pintype "passive"))
      (node (ref "K7") (pin "5") (pinfunction "T2_5") (pintype "passive"))
      (node (ref "K9") (pin "5") (pinfunction "T2_5") (pintype "passive"))
      (node (ref "P1") (pin "4") (pinfunction "4_4") (pintype "passive"))
      (node (ref "Q1") (pin "2") (pinfunction "E_2") (pintype "passive"))
      (node (ref "Q11") (pin "2") (pinfunction "E_2") (pintype "passive"))
      (node (ref "Q13") (pin "2") (pinfunction "E_2") (pintype "passive"))
      (node (ref "Q15") (pin "2") (pinfunction "E_2") (pintype "passive"))
      (node (ref "Q3") (pin "2") (pinfunction "E_2") (pintype "passive"))
      (node (ref "Q5") (pin "2") (pinfunction "E_2") (pintype "passive"))
      (node (ref "Q7") (pin "2") (pinfunction "E_2") (pintype "passive"))
      (node (ref "Q9") (pin "2") (pinfunction "E_2") (pintype "passive"))
      (node (ref "R1") (pin "2") (pinfunction "2_2") (pintype "passive"))
      (node (ref "R10") (pin "1") (pinfunction "1_1") (pintype "passive"))
      (node (ref "R14") (pin "1") (pinfunction "1_1") (pintype "passive"))
      (node (ref "R18") (pin "1") (pinfunction "1_1") (pintype "passive"))
      (node (ref "R22") (pin "1") (pinfunction "1_1") (pintype "passive"))
      (node (ref "R26") (pin "1") (pinfunction "1_1") (pintype "passive"))
      (node (ref "R30") (pin "1") (pinfunction "1_1") (pintype "passive"))
      (node (ref "R34") (pin "1") (pinfunction "1_1") (pintype "passive"))
      (node (ref "R38") (pin "1") (pinfunction "1_1") (pintype "passive"))
      (node (ref "R8") (pin "1") (pinfunction "1_1") (pintype "passive"))
      (node (ref "U1") (pin "18") (pinfunction "GND_18") (pintype "passive"))
      (node (ref "U1") (pin "21") (pinfunction "GND_21") (pintype "passive"))
      (node (ref "U1") (pin "25") (pinfunction "AGND_25") (pintype "passive"))
      (node (ref "U1") (pin "26") (pinfunction "TEST_26") (pintype "passive"))
      (node (ref "U1") (pin "7") (pinfunction "GND_7") (pintype "passive"))
      (node (ref "U2") (pin "15") (pinfunction "VSS_15") (pintype "passive"))
      (node (ref "USB_TypeB1") (pin "4") (pinfunction "GND_4") (pintype "passive"))
      (node (ref "VR1") (pin "1") (pinfunction "GND_1") (pintype "passive"))
    )
    (net (code "40") (name "Net-(C1-Pad1)") (class "Default")
      (node (ref "C1") (pin "1") (pinfunction "1_1") (pintype "passive"))
      (node (ref "R1") (pin "1") (pinfunction "1_1") (pintype "passive"))
      (node (ref "USB_TypeB1") (pin "5") (pinfunction "NC_5") (pintype "passive"))
      (node (ref "USB_TypeB1") (pin "6") (pinfunction "NC_6") (pintype "passive"))
    )
    (net (code "41") (name "Net-(D1-PadK)") (class "Default")
      (node (ref "D1") (pin "K") (pinfunction "K_K") (pintype "passive"))
      (node (ref "R4") (pin "1") (pinfunction "1_1") (pintype "passive"))
    )
    (net (code "42") (name "Net-(D2-PadK)") (class "Default")
      (node (ref "D2") (pin "K") (pinfunction "K_K") (pintype "passive"))
      (node (ref "R5") (pin "2") (pinfunction "2_2") (pintype "passive"))
    )
    (net (code "43") (name "Net-(D3-PadA)") (class "Default")
      (node (ref "D3") (pin "A") (pinfunction "A_A") (pintype "passive"))
      (node (ref "R7") (pin "2") (pinfunction "2_2") (pintype "passive"))
    )
    (net (code "44") (name "Net-(D4-PadK)") (class "Default")
      (node (ref "D4") (pin "K") (pinfunction "K_K") (pintype "passive"))
      (node (ref "R9") (pin "1") (pinfunction "1_1") (pintype "passive"))
    )
    (net (code "45") (name "Net-(D5-PadA)") (class "Default")
      (node (ref "D5") (pin "A") (pinfunction "A_A") (pintype "passive"))
      (node (ref "R13") (pin "2") (pinfunction "2_2") (pintype "passive"))
    )
    (net (code "46") (name "Net-(D7-PadA)") (class "Default")
      (node (ref "D7") (pin "A") (pinfunction "A_A") (pintype "passive"))
      (node (ref "R17") (pin "2") (pinfunction "2_2") (pintype "passive"))
    )
    (net (code "47") (name "Net-(D9-PadA)") (class "Default")
      (node (ref "D9") (pin "A") (pinfunction "A_A") (pintype "passive"))
      (node (ref "R21") (pin "2") (pinfunction "2_2") (pintype "passive"))
    )
    (net (code "48") (name "Net-(D11-PadA)") (class "Default")
      (node (ref "D11") (pin "A") (pinfunction "A_A") (pintype "passive"))
      (node (ref "R25") (pin "2") (pinfunction "2_2") (pintype "passive"))
    )
    (net (code "49") (name "Net-(D13-PadA)") (class "Default")
      (node (ref "D13") (pin "A") (pinfunction "A_A") (pintype "passive"))
      (node (ref "R29") (pin "2") (pinfunction "2_2") (pintype "passive"))
    )
    (net (code "50") (name "Net-(D15-PadA)") (class "Default")
      (node (ref "D15") (pin "A") (pinfunction "A_A") (pintype "passive"))
      (node (ref "R33") (pin "2") (pinfunction "2_2") (pintype "passive"))
    )
    (net (code "51") (name "Net-(D17-PadA)") (class "Default")
      (node (ref "D17") (pin "A") (pinfunction "A_A") (pintype "passive"))
      (node (ref "R37") (pin "2") (pinfunction "2_2") (pintype "passive"))
    )
    (net (code "52") (name "Net-(D19-PadA)") (class "Default")
      (node (ref "D19") (pin "A") (pinfunction "A_A") (pintype "passive"))
      (node (ref "R41") (pin "2") (pinfunction "2_2") (pintype "passive"))
    )
    (net (code "53") (name "Net-(K10-NO)") (class "Default")
      (node (ref "K10") (pin "3") (pinfunction "NO_3") (pintype "passive"))
      (node (ref "R42") (pin "1") (pinfunction "1_1") (pintype "passive"))
    )
    (net (code "54") (name "Net-(Q1-B)") (class "Default")
      (node (ref "Q1") (pin "1") (pinfunction "B_1") (pintype "passive"))
      (node (ref "R11") (pin "1") (pinfunction "1_1") (pintype "passive"))
    )
    (net (code "55") (name "Net-(Q1-C)") (class "Default")
      (node (ref "Q1") (pin "3") (pinfunction "C_3") (pintype "passive"))
      (node (ref "R12") (pin "1") (pinfunction "1_1") (pintype "passive"))
    )
    (net (code "56") (name "Net-(Q2-B)") (class "Default")
      (node (ref "Q2") (pin "1") (pinfunction "B_1") (pintype "passive"))
      (node (ref "R12") (pin "2") (pinfunction "2_2") (pintype "passive"))
    )
    (net (code "57") (name "Net-(Q3-B)") (class "Default")
      (node (ref "Q3") (pin "1") (pinfunction "B_1") (pintype "passive"))
      (node (ref "R15") (pin "1") (pinfunction "1_1") (pintype "passive"))
    )
    (net (code "58") (name "Net-(Q3-C)") (class "Default")
      (node (ref "Q3") (pin "3") (pinfunction "C_3") (pintype "passive"))
      (node (ref "R16") (pin "1") (pinfunction "1_1") (pintype "passive"))
    )
    (net (code "59") (name "Net-(Q4-B)") (class "Default")
      (node (ref "Q4") (pin "1") (pinfunction "B_1") (pintype "passive"))
      (node (ref "R16") (pin "2") (pinfunction "2_2") (pintype "passive"))
    )
    (net (code "60") (name "Net-(Q5-B)") (class "Default")
      (node (ref "Q5") (pin "1") (pinfunction "B_1") (pintype "passive"))
      (node (ref "R19") (pin "1") (pinfunction "1_1") (pintype "passive"))
    )
    (net (code "61") (name "Net-(Q5-C)") (class "Default")
      (node (ref "Q5") (pin "3") (pinfunction "C_3") (pintype "passive"))
      (node (ref "R20") (pin "1") (pinfunction "1_1") (pintype "passive"))
    )
    (net (code "62") (name "Net-(Q6-B)") (class "Default")
      (node (ref "Q6") (pin "1") (pinfunction "B_1") (pintype "passive"))
      (node (ref "R20") (pin "2") (pinfunction "2_2") (pintype "passive"))
    )
    (net (code "63") (name "Net-(Q7-B)") (class "Default")
      (node (ref "Q7") (pin "1") (pinfunction "B_1") (pintype "passive"))
      (node (ref "R23") (pin "1") (pinfunction "1_1") (pintype "passive"))
    )
    (net (code "64") (name "Net-(Q7-C)") (class "Default")
      (node (ref "Q7") (pin "3") (pinfunction "C_3") (pintype "passive"))
      (node (ref "R24") (pin "1") (pinfunction "1_1") (pintype "passive"))
    )
    (net (code "65") (name "Net-(Q8-B)") (class "Default")
      (node (ref "Q8") (pin "1") (pinfunction "B_1") (pintype "passive"))
      (node (ref "R24") (pin "2") (pinfunction "2_2") (pintype "passive"))
    )
    (net (code "66") (name "Net-(Q9-B)") (class "Default")
      (node (ref "Q9") (pin "1") (pinfunction "B_1") (pintype "passive"))
      (node (ref "R27") (pin "1") (pinfunction "1_1") (pintype "passive"))
    )
    (net (code "67") (name "Net-(Q9-C)") (class "Default")
      (node (ref "Q9") (pin "3") (pinfunction "C_3") (pintype "passive"))
      (node (ref "R28") (pin "1") (pinfunction "1_1") (pintype "passive"))
    )
    (net (code "68") (name "Net-(Q10-B)") (class "Default")
      (node (ref "Q10") (pin "1") (pinfunction "B_1") (pintype "passive"))
      (node (ref "R28") (pin "2") (pinfunction "2_2") (pintype "passive"))
    )
    (net (code "69") (name "Net-(Q11-B)") (class "Default")
      (node (ref "Q11") (pin "1") (pinfunction "B_1") (pintype "passive"))
      (node (ref "R31") (pin "1") (pinfunction "1_1") (pintype "passive"))
    )
    (net (code "70") (name "Net-(Q11-C)") (class "Default")
      (node (ref "Q11") (pin "3") (pinfunction "C_3") (pintype "passive"))
      (node (ref "R32") (pin "1") (pinfunction "1_1") (pintype "passive"))
    )
    (net (code "71") (name "Net-(Q12-B)") (class "Default")
      (node (ref "Q12") (pin "1") (pinfunction "B_1") (pintype "passive"))
      (node (ref "R32") (pin "2") (pinfunction "2_2") (pintype "passive"))
    )
    (net (code "72") (name "Net-(Q13-B)") (class "Default")
      (node (ref "Q13") (pin "1") (pinfunction "B_1") (pintype "passive"))
      (node (ref "R35") (pin "1") (pinfunction "1_1") (pintype "passive"))
    )
    (net (code "73") (name "Net-(Q13-C)") (class "Default")
      (node (ref "Q13") (pin "3") (pinfunction "C_3") (pintype "passive"))
      (node (ref "R36") (pin "1") (pinfunction "1_1") (pintype "passive"))
    )
    (net (code "74") (name "Net-(Q14-B)") (class "Default")
      (node (ref "Q14") (pin "1") (pinfunction "B_1") (pintype "passive"))
      (node (ref "R36") (pin "2") (pinfunction "2_2") (pintype "passive"))
    )
    (net (code "75") (name "Net-(Q15-B)") (class "Default")
      (node (ref "Q15") (pin "1") (pinfunction "B_1") (pintype "passive"))
      (node (ref "R39") (pin "1") (pinfunction "1_1") (pintype "passive"))
    )
    (net (code "76") (name "Net-(Q15-C)") (class "Default")
      (node (ref "Q15") (pin "3") (pinfunction "C_3") (pintype "passive"))
      (node (ref "R40") (pin "1") (pinfunction "1_1") (pintype "passive"))
    )
    (net (code "77") (name "Net-(Q16-B)") (class "Default")
      (node (ref "Q16") (pin "1") (pinfunction "B_1") (pintype "passive"))
      (node (ref "R40") (pin "2") (pinfunction "2_2") (pintype "passive"))
    )
    (net (code "78") (name "Net-(U1-CBUS0)") (class "Default")
      (node (ref "R4") (pin "2") (pinfunction "2_2") (pintype "passive"))
      (node (ref "U1") (pin "23") (pinfunction "CBUS0_23") (pintype "passive"))
    )
    (net (code "79") (name "Net-(U1-CBUS1)") (class "Default")
      (node (ref "R5") (pin "1") (pinfunction "1_1") (pintype "passive"))
      (node (ref "U1") (pin "22") (pinfunction "CBUS1_22") (pintype "passive"))
    )
    (net (code "80") (name "Net-(U1-RESET#)") (class "Default")
      (node (ref "C3") (pin "1") (pinfunction "1_1") (pintype "passive"))
      (node (ref "R6") (pin "1") (pinfunction "1_1") (pintype "passive"))
      (node (ref "U1") (pin "19") (pinfunction "RESET#_19") (pintype "passive"))
    )
    (net (code "81") (name "Net-(U1-RXD)") (class "Default")
      (node (ref "R3") (pin "2") (pinfunction "2_2") (pintype "passive"))
      (node (ref "U1") (pin "5") (pinfunction "RXD_5") (pintype "passive"))
    )
    (net (code "82") (name "Net-(U1-TXD)") (class "Default")
      (node (ref "R2") (pin "2") (pinfunction "2_2") (pintype "passive"))
      (node (ref "U1") (pin "1") (pinfunction "TXD_1") (pintype "passive"))
    )
    (net (code "83") (name "Net-(U1-VCC)") (class "Default")
      (node (ref "C4") (pin "2") (pinfunction "2_2") (pintype "passive"))
      (node (ref "C5") (pin "2") (pinfunction "2_2") (pintype "passive"))
      (node (ref "D1") (pin "A") (pinfunction "A_A") (pintype "passive"))
      (node (ref "D2") (pin "A") (pinfunction "A_A") (pintype "passive"))
      (node (ref "FB1") (pin "1") (pinfunction "1_1") (pintype "passive"))
      (node (ref "R6") (pin "2") (pinfunction "2_2") (pintype "passive"))
      (node (ref "U1") (pin "20") (pinfunction "VCC_20") (pintype "passive"))
    )
    (net (code "84") (name "Net-(U2-BOOT0)") (class "Default")
      (node (ref "R8") (pin "2") (pinfunction "2_2") (pintype "passive"))
      (node (ref "U2") (pin "1") (pinfunction "BOOT0_1") (pintype "passive"))
    )
    (net (code "85") (name "Net-(U2-NRST)") (class "Default")
      (node (ref "C9") (pin "1") (pinfunction "1_1") (pintype "passive"))
      (node (ref "U2") (pin "4") (pinfunction "NRST_4") (pintype "passive"))
    )
    (net (code "86") (name "unconnected-(K1-NC-Pad2)") (class "Default")
      (node (ref "K1") (pin "2") (pinfunction "NC_2") (pintype "passive"))
    )
    (net (code "87") (name "unconnected-(K2-NC-Pad2)") (class "Default")
      (node (ref "K2") (pin "2") (pinfunction "NC_2") (pintype "passive"))
    )
    (net (code "88") (name "unconnected-(K4-NC-Pad2)") (class "Default")
      (node (ref "K4") (pin "2") (pinfunction "NC_2") (pintype "passive"))
    )
    (net (code "89") (name "unconnected-(K5-NC-Pad2)") (class "Default")
      (node (ref "K5") (pin "2") (pinfunction "NC_2") (pintype "passive"))
    )
    (net (code "90") (name "unconnected-(K6-NC-Pad2)") (class "Default")
      (node (ref "K6") (pin "2") (pinfunction "NC_2") (pintype "passive"))
    )
    (net (code "91") (name "unconnected-(K7-NC-Pad2)") (class "Default")
      (node (ref "K7") (pin "2") (pinfunction "NC_2") (pintype "passive"))
    )
    (net (code "92") (name "unconnected-(K9-NC-Pad2)") (class "Default")
      (node (ref "K9") (pin "2") (pinfunction "NC_2") (pintype "passive"))
    )
    (net (code "93") (name "unconnected-(K10-NC-Pad2)") (class "Default")
      (node (ref "K10") (pin "2") (pinfunction "NC_2") (pintype "passive"))
    )
    (net (code "94") (name "unconnected-(U1-CBUS2-Pad14)") (class "Default")
      (node (ref "U1") (pin "14") (pinfunction "CBUS2_14") (pintype "passive"))
    )
    (net (code "95") (name "unconnected-(U1-CBUS3-Pad13)") (class "Default")
      (node (ref "U1") (pin "13") (pinfunction "CBUS3_13") (pintype "passive"))
    )
    (net (code "96") (name "unconnected-(U1-CBUS4-Pad12)") (class "Default")
      (node (ref "U1") (pin "12") (pinfunction "CBUS4_12") (pintype "passive"))
    )
    (net (code "97") (name "unconnected-(U1-CTS#-Pad11)") (class "Default")
      (node (ref "U1") (pin "11") (pinfunction "CTS#_11") (pintype "passive"))
    )
    (net (code "98") (name "unconnected-(U1-DCD#-Pad10)") (class "Default")
      (node (ref "U1") (pin "10") (pinfunction "DCD#_10") (pintype "passive"))
    )
    (net (code "99") (name "unconnected-(U1-DSR#-Pad9)") (class "Default")
      (node (ref "U1") (pin "9") (pinfunction "DSR#_9") (pintype "passive"))
    )
    (net (code "100") (name "unconnected-(U1-DTR#-Pad2)") (class "Default")
      (node (ref "U1") (pin "2") (pinfunction "DTR#_2") (pintype "passive"))
    )
    (net (code "101") (name "unconnected-(U1-NC-Pad8)") (class "Default")
      (node (ref "U1") (pin "8") (pinfunction "NC_8") (pintype "passive"))
    )
    (net (code "102") (name "unconnected-(U1-NC-Pad24)") (class "Default")
      (node (ref "U1") (pin "24") (pinfunction "NC_24") (pintype "passive"))
    )
    (net (code "103") (name "unconnected-(U1-OSCI-Pad27)") (class "Default")
      (node (ref "U1") (pin "27") (pinfunction "OSCI_27") (pintype "passive"))
    )
    (net (code "104") (name "unconnected-(U1-OSCO-Pad28)") (class "Default")
      (node (ref "U1") (pin "28") (pinfunction "OSCO_28") (pintype "passive"))
    )
    (net (code "105") (name "unconnected-(U1-RI#-Pad6)") (class "Default")
      (node (ref "U1") (pin "6") (pinfunction "RI#_6") (pintype "passive"))
    )
    (net (code "106") (name "unconnected-(U1-RTS#-Pad3)") (class "Default")
      (node (ref "U1") (pin "3") (pinfunction "RTS#_3") (pintype "passive"))
    )
  )
)
